# RS485.net
KiCad netlist of a schematic drawn in Altium Designer
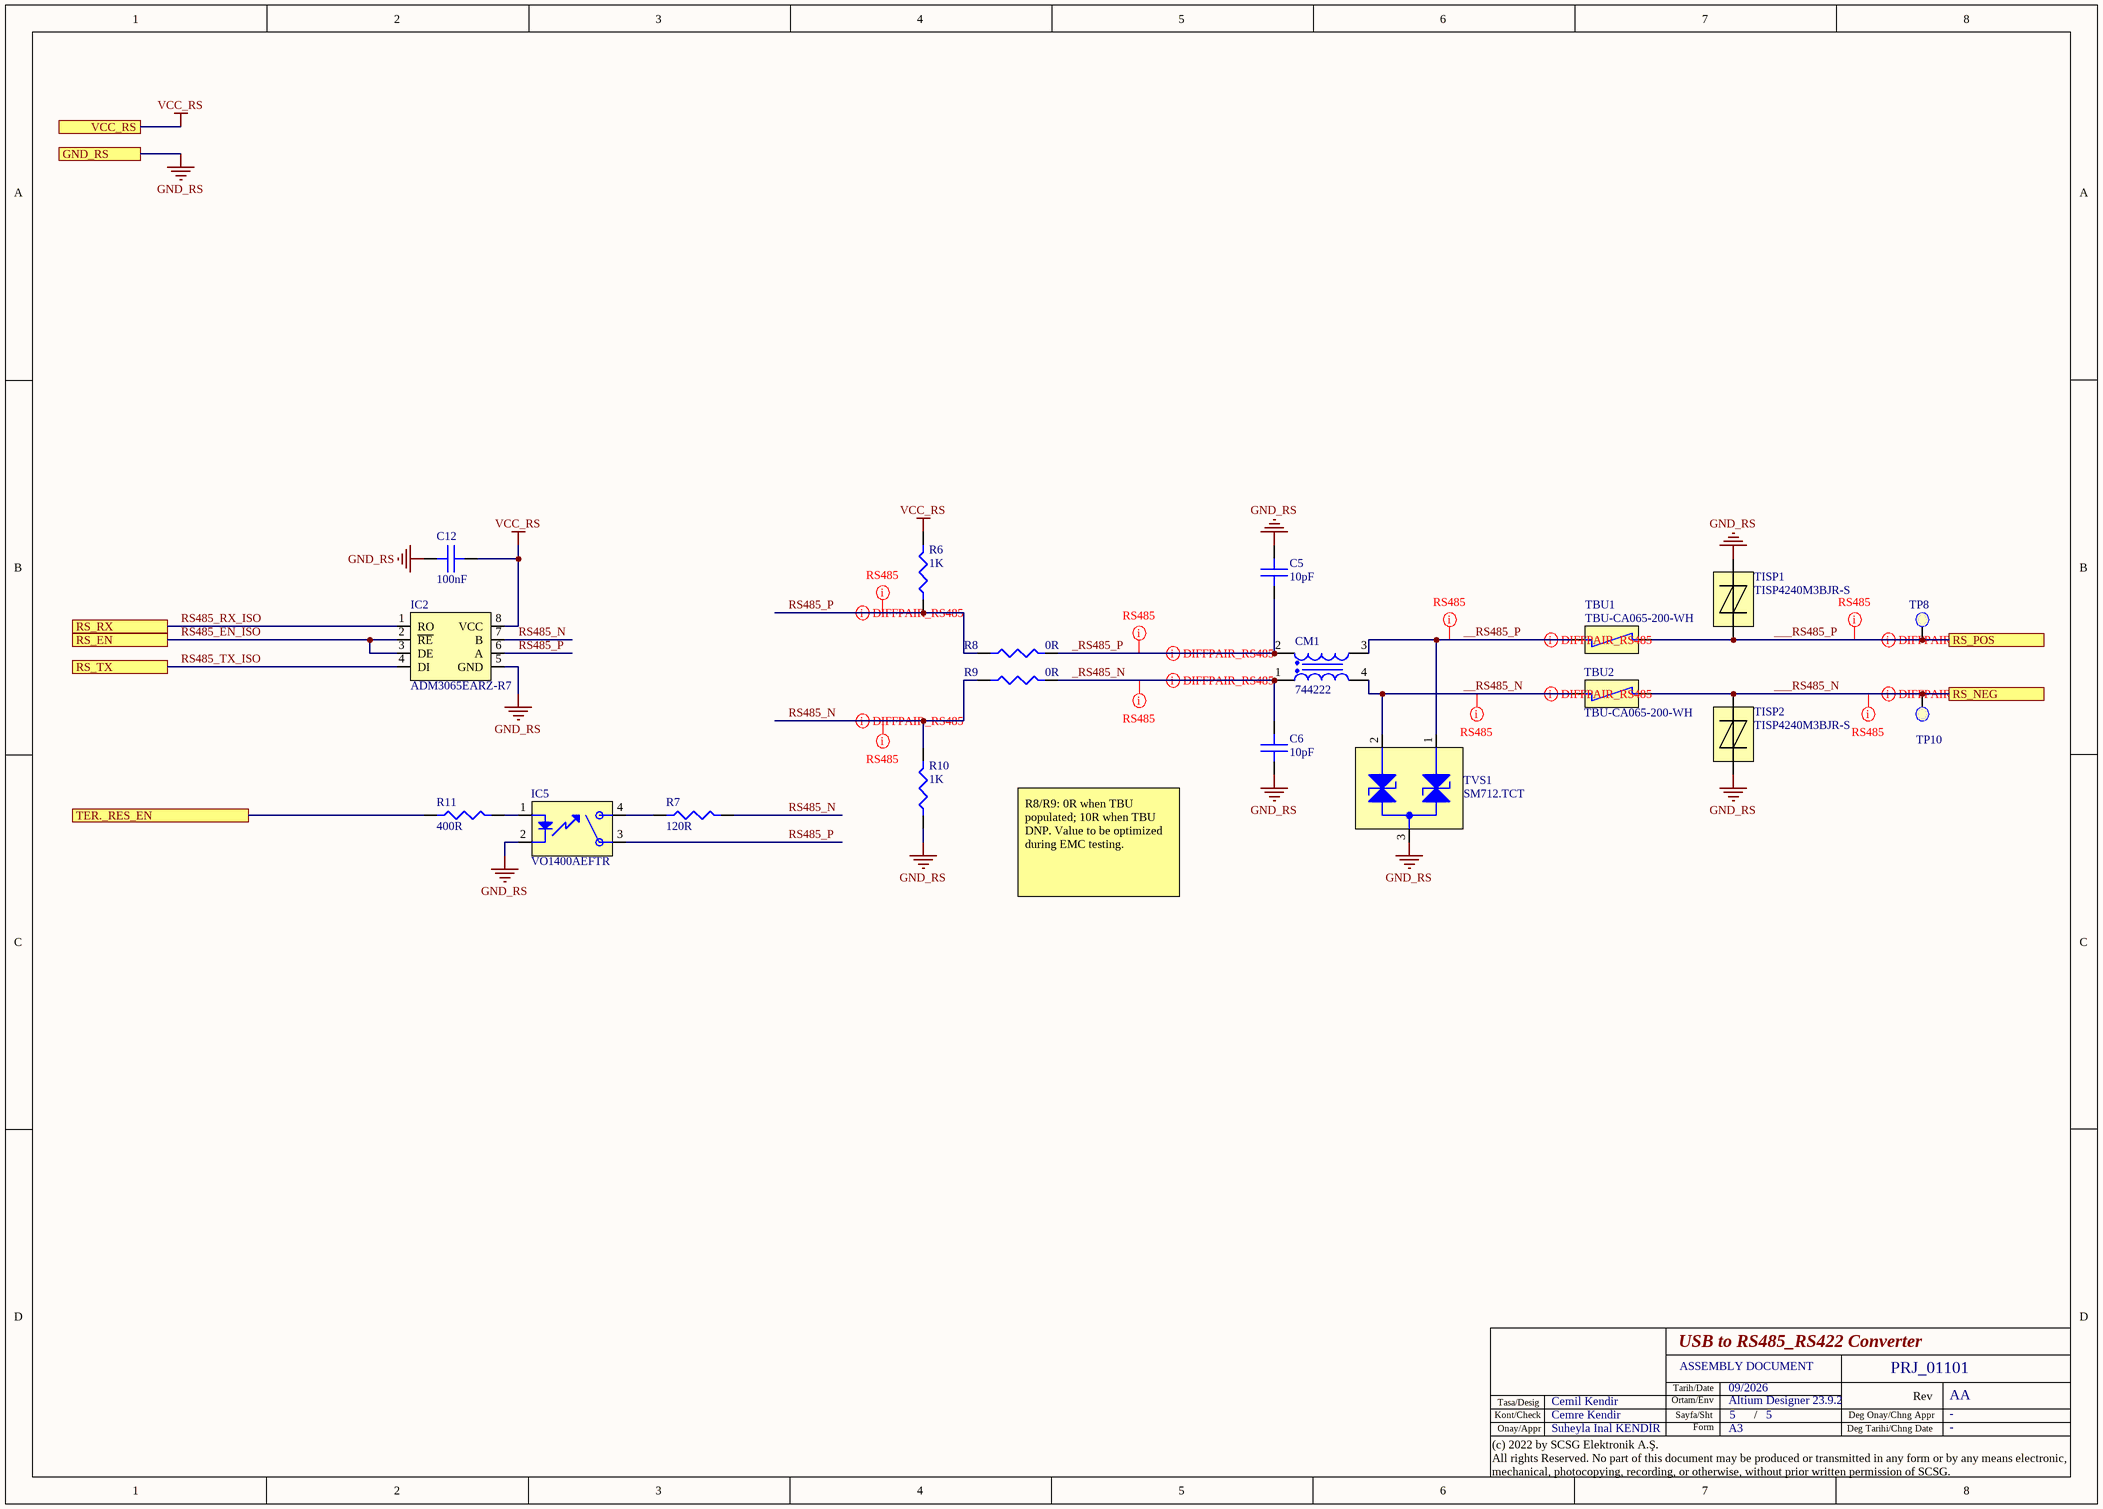
[diagram p0: RS485.SchDoc]

(export (version "E")
  (design (tool "Eeschema 10.0.6"))
  (components
    (comp (ref "C5")
      (value "10pF")
      (footprint "C0402")
      (description "10pF, 50V, NP0, 0402")
      (fields
        (field (name "MANUFACTURER") "Yageo")
        (field (name "MANUFACTURER PART NUMBER") "CC0402JRNPO9BN100")
      )
      (libsource (lib "Capacitor") (part "CC0402JRNPO9BN100"))
    )
    (comp (ref "C6")
      (value "10pF")
      (footprint "C0402")
      (description "10pF, 50V, NP0, 0402")
      (fields
        (field (name "MANUFACTURER") "Yageo")
        (field (name "MANUFACTURER PART NUMBER") "CC0402JRNPO9BN100")
      )
      (libsource (lib "Capacitor") (part "CC0402JRNPO9BN100"))
    )
    (comp (ref "C12")
      (value "100nF")
      (footprint "C0603")
      (description "100nF, 25V, X7R, 0603")
      (fields
        (field (name "MANUFACTURER") "Yageo")
        (field (name "MANUFACTURER PART NUMBER") "CC0603KRX7R8BB104")
      )
      (libsource (lib "Capacitor") (part "CC0603KRX7R8BB104"))
    )
    (comp (ref "CM1")
      (value "744222")
      (footprint "WE-SL2_74422")
      (description "Common Mode Chokes Dual 1000uH 6kOhm 100kHz 0.8A 0.207Ohm DCR SMD T/R Automotive AEC-Q200")
      (fields (field (name "MANUFACTURER") "Wurth Elektronik"))
      (libsource (lib "Inductor") (part "744222"))
    )
    (comp (ref "IC2")
      (value "ADM3065EARZ-R7")
      (footprint "SO08")
      (description "3.0 V to 5.5 V, ±12 kV IEC ESD Protected, Half Duplex 50 Mbps RS-485 Transceiver")
      (fields (field (name "MANUFACTURER") "Analog Devices"))
      (libsource (lib "IntegratedCircuit") (part "ADM3065EARZ-R7"))
    )
    (comp (ref "IC5")
      (value "VO1400AEFTR")
      (footprint "SOP-4")
      (description "1 FORM A SOLID STATE RELAY Transistor Output SSR, 1-Channel, 3750V Isolation")
      (fields (field (name "MANUFACTURER") "Vishay"))
      (libsource (lib "IntegratedCircuit") (part "VO1400AEFTR"))
    )
    (comp (ref "R6")
      (value "1K")
      (footprint "R0805")
      (description "1K, %5, 1/8W, 0805")
      (fields
        (field (name "MANUFACTURER") "YAGEO")
        (field (name "MANUFACTURER PART NUMBER") "RC0805JR-071KL")
      )
      (libsource (lib "Resistor") (part "RC0805JR-071KL"))
    )
    (comp (ref "R7")
      (value "120R")
      (footprint "R0805")
      (description "120R, %5, 1/8W, 0805")
      (fields
        (field (name "MANUFACTURER") "YAGEO")
        (field (name "MANUFACTURER PART NUMBER") "RC0805JR-07120RL")
      )
      (libsource (lib "Resistor") (part "RC0805JR-07120RL"))
    )
    (comp (ref "R8")
      (value "0R")
      (footprint "R0603")
      (description "0R ,%1 ,1/10 W ,0603")
      (fields
        (field (name "MANUFACTURER") "YAGEO")
        (field (name "MANUFACTURER PART NUMBER") "RC0603FR-070RL")
      )
      (libsource (lib "Resistor") (part "RC0603FR-070RL"))
    )
    (comp (ref "R9")
      (value "0R")
      (footprint "R0603")
      (description "0R ,%1 ,1/10 W ,0603")
      (fields
        (field (name "MANUFACTURER") "YAGEO")
        (field (name "MANUFACTURER PART NUMBER") "RC0603FR-070RL")
      )
      (libsource (lib "Resistor") (part "RC0603FR-070RL"))
    )
    (comp (ref "R10")
      (value "1K")
      (footprint "R0805")
      (description "1K, %5, 1/8W, 0805")
      (fields
        (field (name "MANUFACTURER") "YAGEO")
        (field (name "MANUFACTURER PART NUMBER") "RC0805JR-071KL")
      )
      (libsource (lib "Resistor") (part "RC0805JR-071KL"))
    )
    (comp (ref "R11")
      (value "400R")
      (footprint "R0603")
      (description "400R, %0.1, 1/8W, 0603")
      (fields
        (field (name "MANUFACTURER") "Vishay Dale Thin Film")
        (field (name "MANUFACTURER PART NUMBER") "PAT0603E4000BST1")
      )
      (libsource (lib "Resistor") (part "PAT0603E4000BST1"))
    )
    (comp (ref "TBU1")
      (value "TBU-CA065-200-WH")
      (footprint "TBU-CA065-200-WH")
      (description "A Single Bi-Directional, 650V, 200mA, 3-Pin DFN pkg TBU ¦ Bourns TBU-CA065-200-WH")
      (fields (field (name "MANUFACTURER") "Bourns"))
      (libsource (lib "Protection") (part "TBU-CA065-200-WH"))
    )
    (comp (ref "TBU2")
      (value "TBU-CA065-200-WH")
      (footprint "TBU-CA065-200-WH")
      (description "A Single Bi-Directional, 650V, 200mA, 3-Pin DFN pkg TBU ¦ Bourns TBU-CA065-200-WH")
      (fields (field (name "MANUFACTURER") "Bourns"))
      (libsource (lib "Protection") (part "TBU-CA065-200-WH"))
    )
    (comp (ref "TISP1")
      (value "TISP4240M3BJR-S")
      (footprint "SMB/DO-214AA")
      (description "TVS Thyristor, Bidirectional, 2 Pins, DO-214AA (SMB), Overvoltage Protector, 240 V, 1 Circuit")
      (fields (field (name "MANUFACTURER") "Bourns"))
      (libsource (lib "") (part "TISP4240M3BJR-S_1"))
    )
    (comp (ref "TISP2")
      (value "TISP4240M3BJR-S")
      (footprint "SMB/DO-214AA")
      (description "TVS Thyristor, Bidirectional, 2 Pins, DO-214AA (SMB), Overvoltage Protector, 240 V, 1 Circuit")
      (fields (field (name "MANUFACTURER") "Bourns"))
      (libsource (lib "Protection") (part "TISP4240M3BJR-S"))
    )
    (comp (ref "TP8")
      (value "TestPoint1")
      (footprint "SMD_1mmPoint")
      (description "test ölçüm noktası")
      (fields (field (name "MANUFACTURER") "NO BOM DEVICE"))
      (libsource (lib "Connectors") (part "TestPoint1"))
    )
    (comp (ref "TP10")
      (value "TestPoint1")
      (footprint "SMD_1mmPoint")
      (description "test ölçüm noktası")
      (fields (field (name "MANUFACTURER") "NO BOM DEVICE"))
      (libsource (lib "Connectors") (part "TestPoint1"))
    )
    (comp (ref "TVS1")
      (value "SM712.TCT")
      (footprint "WE-TVS_SOT23-3L")
      (description "SM Series 12 V 400 W Asymmetrical TVS Diode for Extended Common-Mode - SOT-23")
      (fields (field (name "MANUFACTURER") "Semtech"))
      (libsource (lib "Protection") (part "SM712.TCT"))
    )
  )
  (nets
    (net (code "1") (name "/RS485_EN_ISO") (class "Default")
      (node (ref "IC2") (pin "2") (pinfunction "~{RE}_2") (pintype "passive"))
      (node (ref "IC2") (pin "3") (pinfunction "DE_3") (pintype "passive"))
    )
    (net (code "2") (name "/RS485_N") (class "Default")
      (node (ref "IC2") (pin "7") (pinfunction "B_7") (pintype "passive"))
      (node (ref "R10") (pin "2") (pinfunction "2_2") (pintype "passive"))
      (node (ref "R7") (pin "2") (pinfunction "2_2") (pintype "passive"))
      (node (ref "R9") (pin "1") (pinfunction "1_1") (pintype "passive"))
    )
    (net (code "3") (name "/RS485_P") (class "Default")
      (node (ref "IC2") (pin "6") (pinfunction "A_6") (pintype "passive"))
      (node (ref "IC5") (pin "3") (pinfunction "3_3") (pintype "passive"))
      (node (ref "R6") (pin "1") (pinfunction "1_1") (pintype "passive"))
      (node (ref "R8") (pin "1") (pinfunction "1_1") (pintype "passive"))
    )
    (net (code "4") (name "/RS485_RX_ISO") (class "Default")
      (node (ref "IC2") (pin "1") (pinfunction "RO_1") (pintype "passive"))
    )
    (net (code "5") (name "/RS485_TX_ISO") (class "Default")
      (node (ref "IC2") (pin "4") (pinfunction "DI_4") (pintype "passive"))
    )
    (net (code "6") (name "/TER._RES_EN") (class "Default")
      (node (ref "R11") (pin "1") (pinfunction "1_1") (pintype "passive"))
    )
    (net (code "7") (name "/_RS485_N") (class "Default")
      (node (ref "C6") (pin "2") (pintype "passive"))
      (node (ref "CM1") (pin "1") (pinfunction "1_1") (pintype "passive"))
      (node (ref "R9") (pin "2") (pinfunction "2_2") (pintype "passive"))
    )
    (net (code "8") (name "/_RS485_P") (class "Default")
      (node (ref "C5") (pin "1") (pintype "passive"))
      (node (ref "CM1") (pin "2") (pinfunction "2_2") (pintype "passive"))
      (node (ref "R8") (pin "2") (pinfunction "2_2") (pintype "passive"))
    )
    (net (code "9") (name "/__RS485_N") (class "Default")
      (node (ref "CM1") (pin "4") (pinfunction "4_4") (pintype "passive"))
      (node (ref "TBU2") (pin "1") (pinfunction "1_1") (pintype "passive"))
      (node (ref "TVS1") (pin "2") (pinfunction "I/O_2_2") (pintype "passive"))
    )
    (net (code "10") (name "/__RS485_P") (class "Default")
      (node (ref "CM1") (pin "3") (pinfunction "3_3") (pintype "passive"))
      (node (ref "TBU1") (pin "1") (pinfunction "1_1") (pintype "passive"))
      (node (ref "TVS1") (pin "1") (pinfunction "I/O_1_1") (pintype "passive"))
    )
    (net (code "11") (name "/___RS485_N") (class "Default")
      (node (ref "TBU2") (pin "2") (pinfunction "2_2") (pintype "passive"))
      (node (ref "TISP2") (pin "2") (pinfunction "2_2") (pintype "passive"))
      (node (ref "TP10") (pin "1") (pinfunction "1_1") (pintype "passive"))
    )
    (net (code "12") (name "/___RS485_P") (class "Default")
      (node (ref "TBU1") (pin "2") (pinfunction "2_2") (pintype "passive"))
      (node (ref "TISP1") (pin "2") (pinfunction "2_2") (pintype "passive"))
      (node (ref "TP8") (pin "1") (pinfunction "1_1") (pintype "passive"))
    )
    (net (code "13") (name "GND_RS") (class "Default")
      (node (ref "C12") (pin "2") (pintype "passive"))
      (node (ref "C5") (pin "2") (pintype "passive"))
      (node (ref "C6") (pin "1") (pintype "passive"))
      (node (ref "IC2") (pin "5") (pinfunction "GND_5") (pintype "passive"))
      (node (ref "IC5") (pin "2") (pinfunction "2_2") (pintype "passive"))
      (node (ref "R10") (pin "1") (pinfunction "1_1") (pintype "passive"))
      (node (ref "TISP1") (pin "1") (pinfunction "1_1") (pintype "passive"))
      (node (ref "TISP2") (pin "1") (pinfunction "1_1") (pintype "passive"))
      (node (ref "TVS1") (pin "3") (pinfunction "GND_3") (pintype "passive"))
    )
    (net (code "14") (name "Net-(IC5-Pad1)") (class "Default")
      (node (ref "IC5") (pin "1") (pinfunction "1_1") (pintype "passive"))
      (node (ref "R11") (pin "2") (pinfunction "2_2") (pintype "passive"))
    )
    (net (code "15") (name "Net-(IC5-Pad4)") (class "Default")
      (node (ref "IC5") (pin "4") (pinfunction "4_4") (pintype "passive"))
      (node (ref "R7") (pin "1") (pinfunction "1_1") (pintype "passive"))
    )
    (net (code "16") (name "VCC_RS") (class "Default")
      (node (ref "C12") (pin "1") (pintype "passive"))
      (node (ref "IC2") (pin "8") (pinfunction "VCC_8") (pintype "passive"))
      (node (ref "R6") (pin "2") (pinfunction "2_2") (pintype "passive"))
    )
  )
)
